# HC-NBIOT_Single_lamp_controller-V1_2.net
KiCad netlist of a schematic drawn in Altium Designer
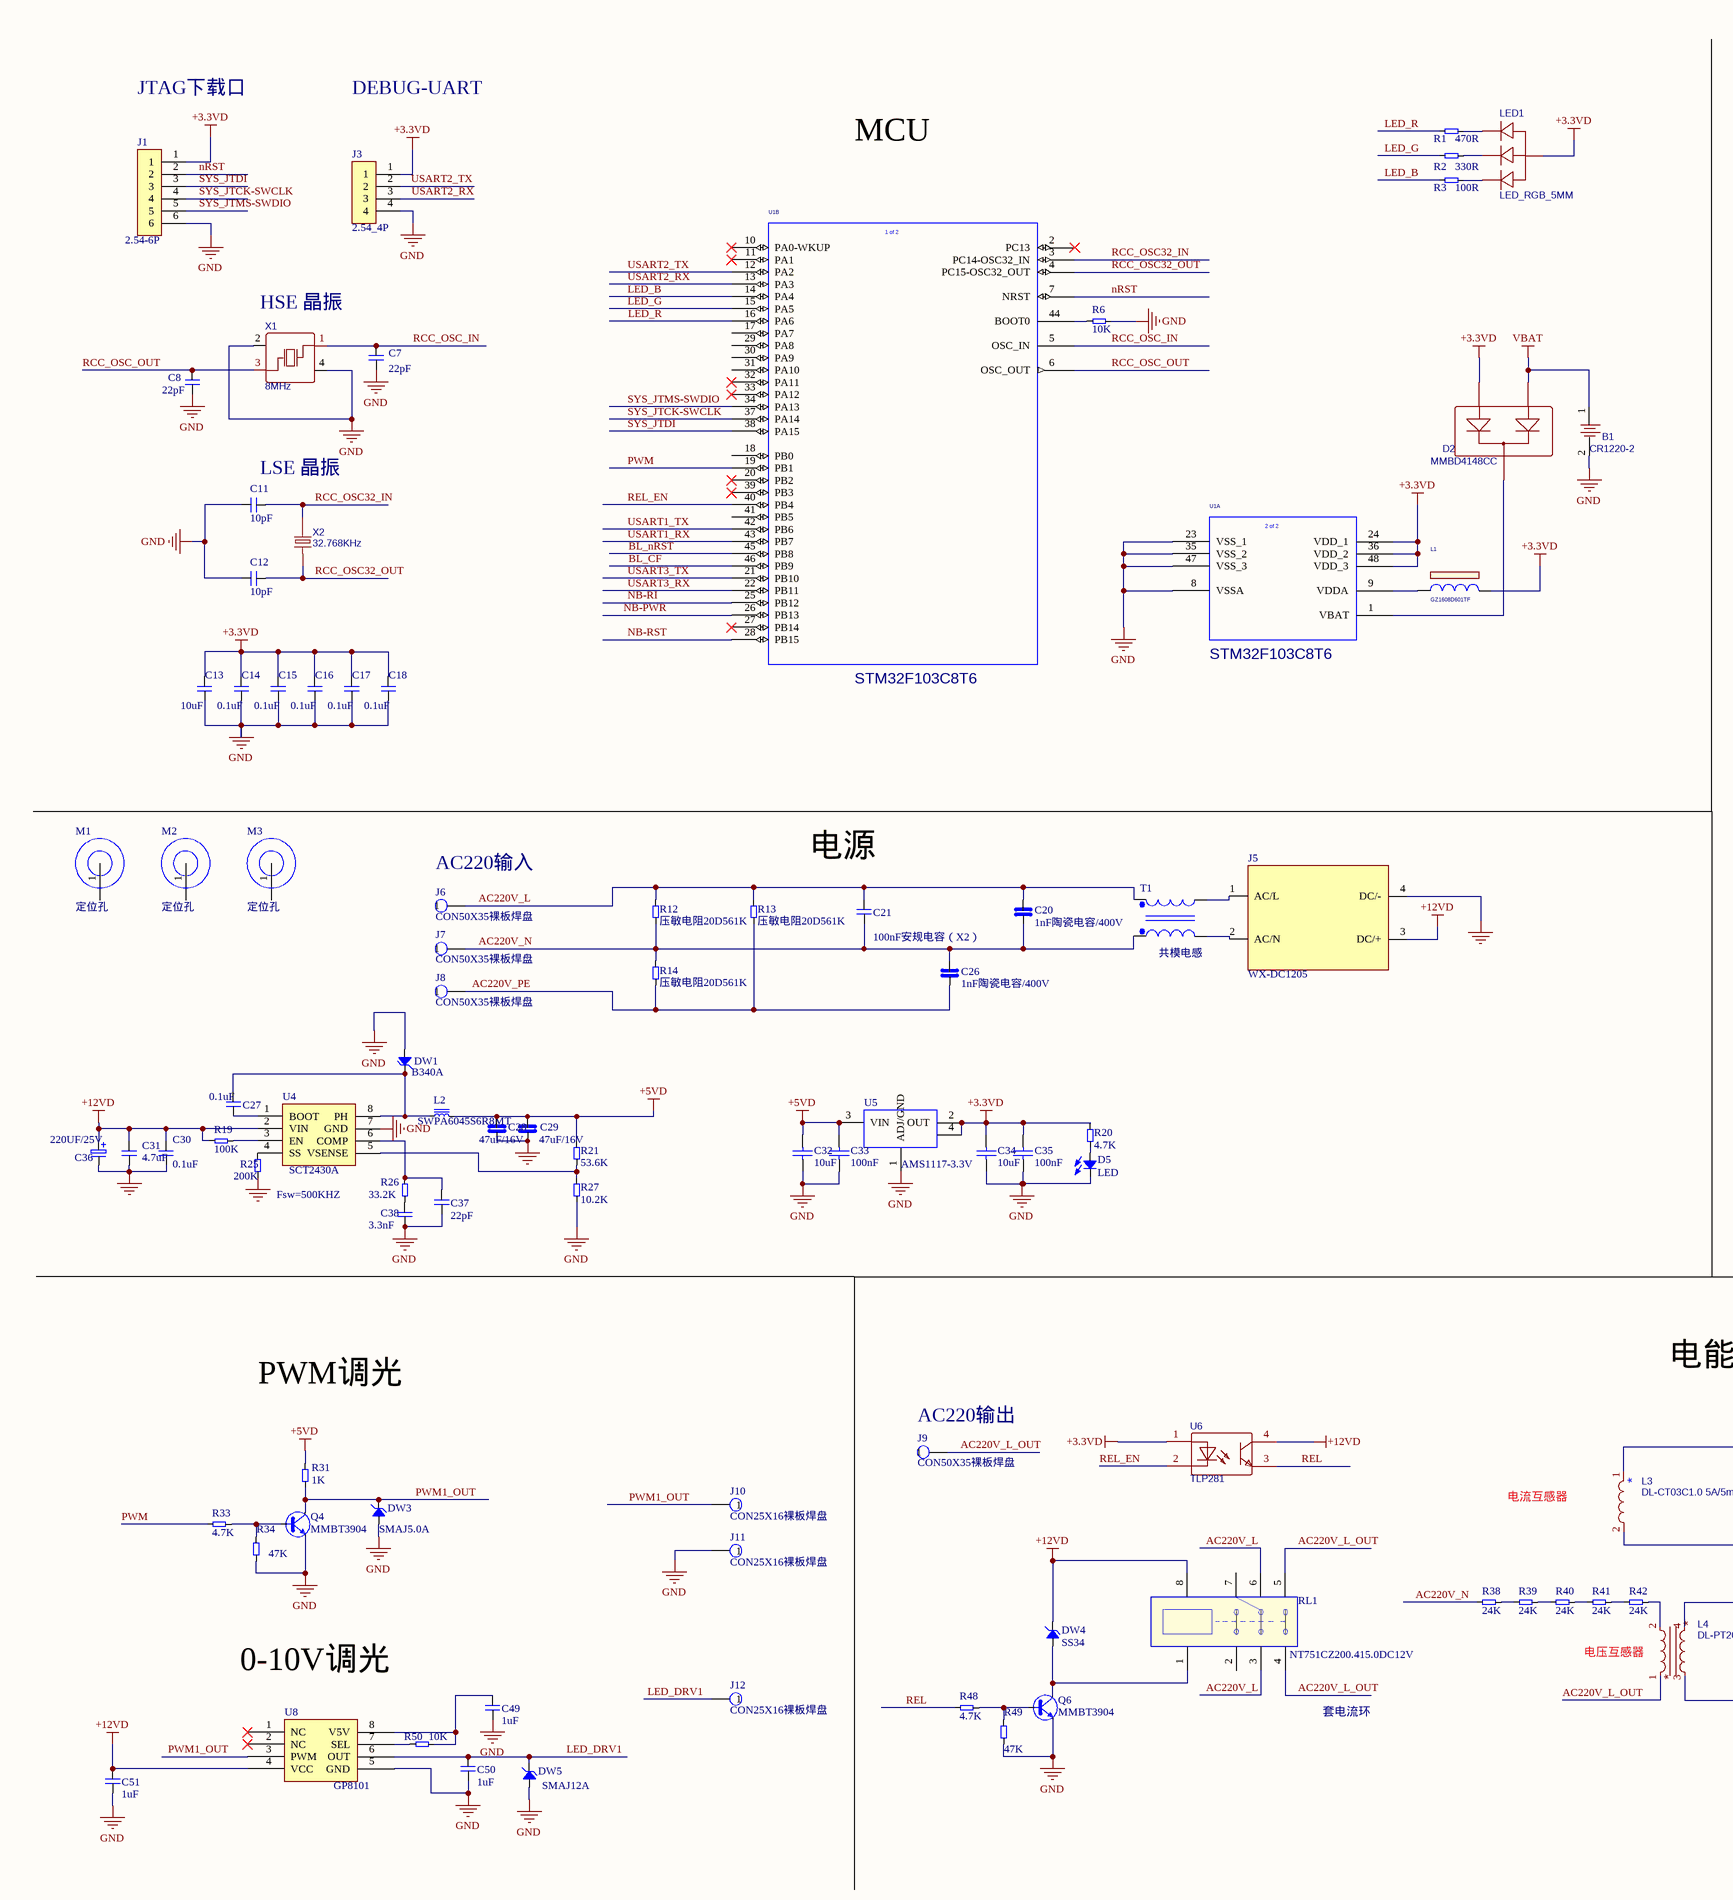
[diagram p0: HC-NBIOT_Single_lamp_controller-V1.2.SchDoc, left]
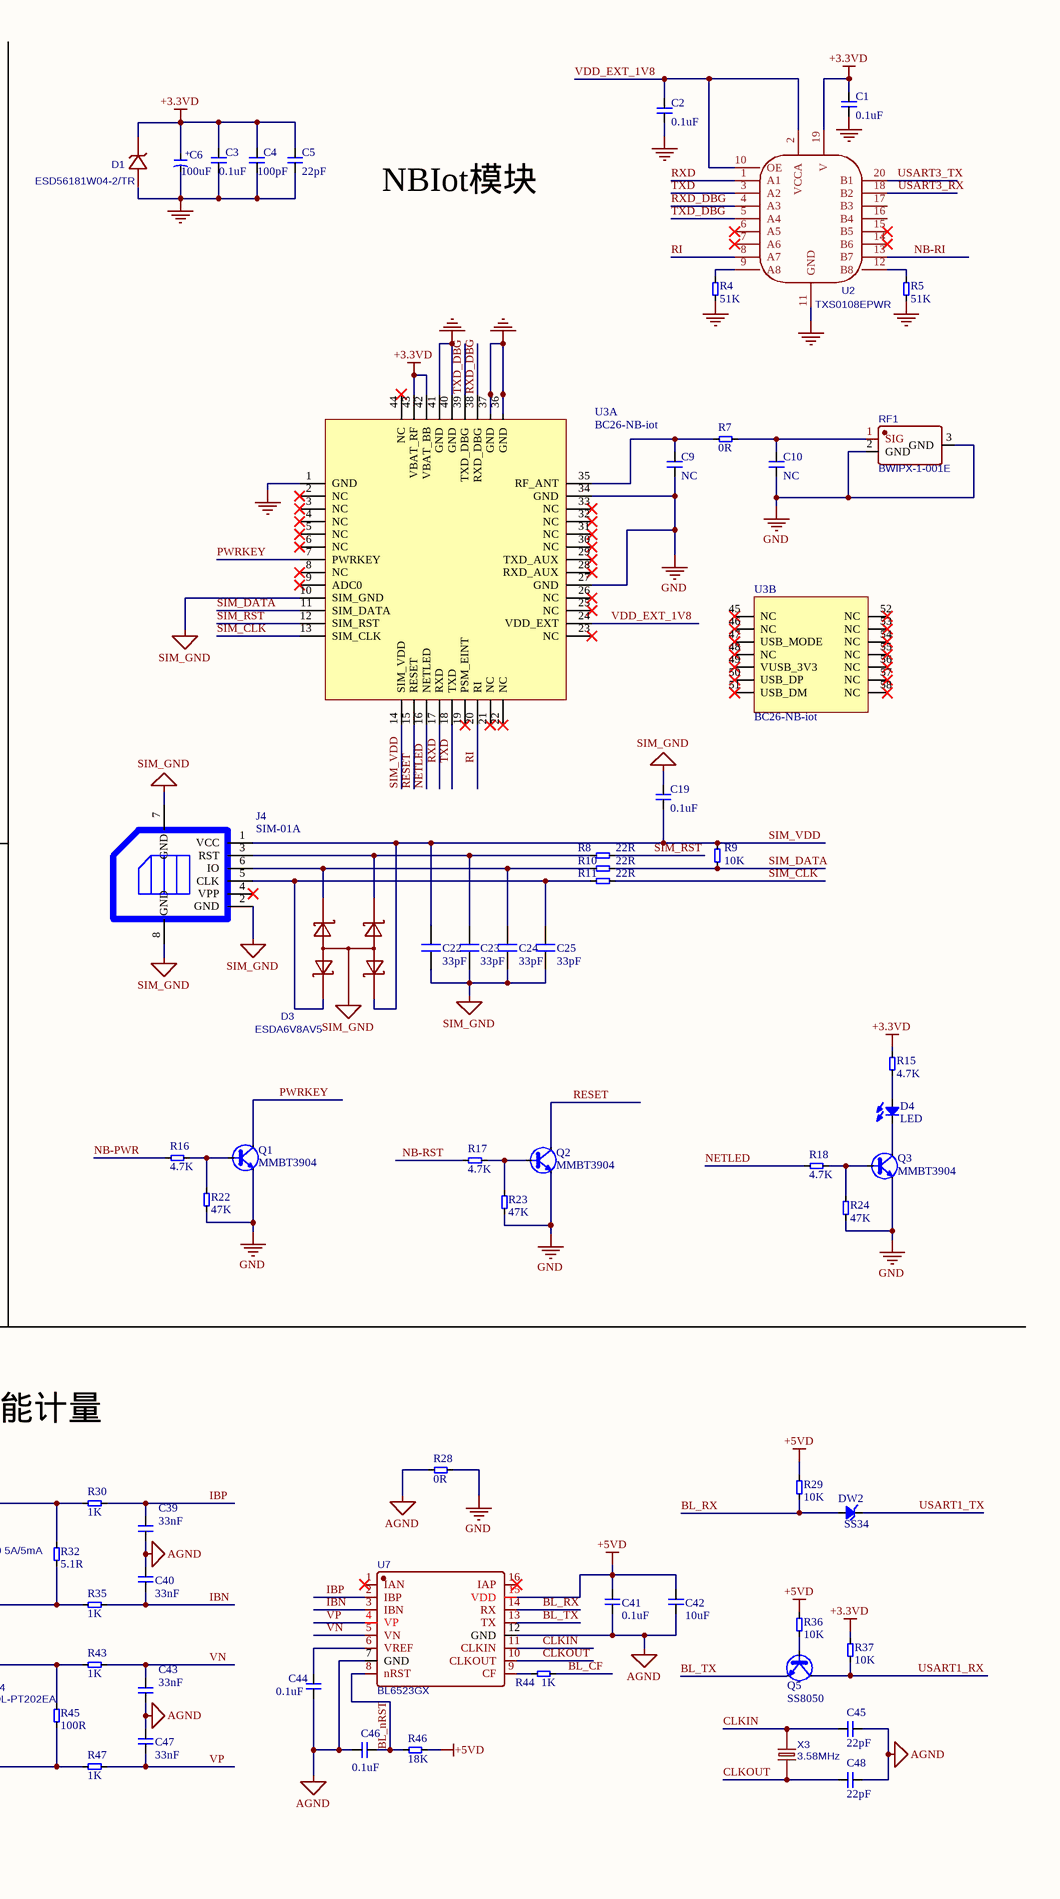
[diagram p1: HC-NBIOT_Single_lamp_controller-V1.2.SchDoc, right]

(export (version "E")
  (design (tool "Eeschema 10.0.6"))
  (components
    (comp (ref "B1")
      (value "CR1220-2")
      (footprint "BAT-SMD_CR1220-2")
      (fields (field (name "BOM_SUPPLIER PART") "C70381"))
      (libsource (lib "czc") (part "CR1220-2"))
    )
    (comp (ref "C1")
      (value "0.1uF")
      (footprint "0603C")
      (description "电容")
      (libsource (lib "DOFAR_AD_LIB") (part "电容"))
    )
    (comp (ref "C2")
      (value "0.1uF")
      (footprint "0603C")
      (description "电容")
      (libsource (lib "DOFAR_AD_LIB") (part "电容"))
    )
    (comp (ref "C3")
      (value "0.1uF")
      (footprint "0603C")
      (description "电容")
      (libsource (lib "DOFAR_AD_LIB") (part "电容"))
    )
    (comp (ref "C4")
      (value "100pF")
      (footprint "0603C")
      (description "电容")
      (libsource (lib "DOFAR_AD_LIB") (part "电容"))
    )
    (comp (ref "C5")
      (value "22pF")
      (footprint "0603C")
      (description "电容")
      (libsource (lib "DOFAR_AD_LIB") (part "电容"))
    )
    (comp (ref "C6")
      (value "100uF")
      (footprint "CAP-SMD_L3.5-W2.8")
      (description "电解电容")
      (libsource (lib "czc") (part "Capacitor"))
    )
    (comp (ref "C7")
      (value "22pF")
      (footprint "0603C")
      (description "电容")
      (libsource (lib "DOFAR_AD_LIB") (part "电容"))
    )
    (comp (ref "C8")
      (value "22pF")
      (footprint "0603C")
      (description "电容")
      (libsource (lib "DOFAR_AD_LIB") (part "电容"))
    )
    (comp (ref "C9")
      (value "NC")
      (footprint "0603C")
      (description "电容")
      (libsource (lib "DOFAR_AD_LIB") (part "电容"))
    )
    (comp (ref "C10")
      (value "NC")
      (footprint "0603C")
      (description "电容")
      (libsource (lib "DOFAR_AD_LIB") (part "电容"))
    )
    (comp (ref "C11")
      (value "10pF")
      (footprint "0603C")
      (description "电容")
      (libsource (lib "DOFAR_AD_LIB") (part "电容"))
    )
    (comp (ref "C12")
      (value "10pF")
      (footprint "0603C")
      (description "电容")
      (libsource (lib "DOFAR_AD_LIB") (part "电容"))
    )
    (comp (ref "C13")
      (value "10uF")
      (footprint "1206C")
      (description "电容")
      (libsource (lib "DOFAR_AD_LIB") (part "电容"))
    )
    (comp (ref "C14")
      (value "0.1uF")
      (footprint "0603C")
      (description "电容")
      (libsource (lib "DOFAR_AD_LIB") (part "电容"))
    )
    (comp (ref "C15")
      (value "0.1uF")
      (footprint "0603C")
      (description "电容")
      (libsource (lib "DOFAR_AD_LIB") (part "电容"))
    )
    (comp (ref "C16")
      (value "0.1uF")
      (footprint "0603C")
      (description "电容")
      (libsource (lib "DOFAR_AD_LIB") (part "电容"))
    )
    (comp (ref "C17")
      (value "0.1uF")
      (footprint "0603C")
      (description "电容")
      (libsource (lib "DOFAR_AD_LIB") (part "电容"))
    )
    (comp (ref "C18")
      (value "0.1uF")
      (footprint "0603C")
      (description "电容")
      (libsource (lib "DOFAR_AD_LIB") (part "电容"))
    )
    (comp (ref "C19")
      (value "0.1uF")
      (footprint "0603C")
      (description "电容")
      (libsource (lib "DOFAR_AD_LIB") (part "电容"))
    )
    (comp (ref "C20")
      (value "1nF陶瓷电容/400V")
      (footprint "1nF/400V")
      (description "多层陶瓷电容")
      (libsource (lib "DF-CBOX-BB_V1.0") (part "多层陶瓷电容"))
    )
    (comp (ref "C21")
      (value "100nF安规电容（X2）")
      (footprint "X2/100nF")
      (description "电容")
      (libsource (lib "DF-CBOX-BB") (part "电容"))
    )
    (comp (ref "C22")
      (value "33pF")
      (footprint "0603C")
      (description "电容")
      (libsource (lib "czc") (part "CAP"))
    )
    (comp (ref "C23")
      (value "33pF")
      (footprint "0603C")
      (description "电容")
      (libsource (lib "czc") (part "CAP"))
    )
    (comp (ref "C24")
      (value "33pF")
      (footprint "0603C")
      (description "电容")
      (libsource (lib "czc") (part "CAP"))
    )
    (comp (ref "C25")
      (value "33pF")
      (footprint "0603C")
      (description "电容")
      (libsource (lib "czc") (part "CAP"))
    )
    (comp (ref "C26")
      (value "1nF陶瓷电容/400V")
      (footprint "1nF/400V")
      (description "多层陶瓷电容")
      (libsource (lib "DF-CBOX-BB_V1.0") (part "多层陶瓷电容"))
    )
    (comp (ref "C27")
      (value "0.1uF")
      (footprint "0603C")
      (description "电容")
      (libsource (lib "DOFAR_AD_LIB") (part "电容"))
    )
    (comp (ref "C28")
      (value "47uF/16V")
      (footprint "1206C")
      (description "多层陶瓷电容")
      (libsource (lib "DOFAR_AD_LIB") (part "多层陶瓷电容"))
    )
    (comp (ref "C29")
      (value "47uF/16V")
      (footprint "1206C")
      (description "多层陶瓷电容")
      (libsource (lib "DOFAR_AD_LIB") (part "多层陶瓷电容"))
    )
    (comp (ref "C30")
      (value "0.1uF")
      (footprint "0603C")
      (description "电容")
      (libsource (lib "DOFAR_AD_LIB") (part "电容"))
    )
    (comp (ref "C31")
      (value "4.7uF")
      (footprint "0603C")
      (description "电容")
      (libsource (lib "*") (part "电容"))
    )
    (comp (ref "C32")
      (value "10uF")
      (footprint "0805C")
      (fields (field (name "PUBLISHER") "Altium Limited"))
      (libsource (lib "Database_AD Library") (part "Cap"))
    )
    (comp (ref "C33")
      (value "100nF")
      (footprint "0603C")
      (fields (field (name "PUBLISHER") "Altium Limited"))
      (libsource (lib "Database_AD Library") (part "Cap"))
    )
    (comp (ref "C34")
      (value "10uF")
      (footprint "0805C")
      (fields (field (name "PUBLISHER") "Altium Limited"))
      (libsource (lib "Database_AD Library") (part "Cap"))
    )
    (comp (ref "C35")
      (value "100nF")
      (footprint "0603C")
      (fields (field (name "PUBLISHER") "Altium Limited"))
      (libsource (lib "Database_AD Library") (part "Cap"))
    )
    (comp (ref "C36")
      (value "220UF/25V")
      (footprint "RAD-3R8")
      (description "电解电容")
      (libsource (lib "DOFAR_AD_LIB") (part "直插电解电容"))
    )
    (comp (ref "C37")
      (value "22pF")
      (footprint "0603C")
      (description "电容")
      (libsource (lib "DOFAR_AD_LIB") (part "电容"))
    )
    (comp (ref "C38")
      (value "3.3nF")
      (footprint "0603C")
      (description "电容")
      (libsource (lib "DOFAR_AD_LIB") (part "电容"))
    )
    (comp (ref "C39")
      (value "33nF")
      (footprint "0603C")
      (description "电容")
      (libsource (lib "DOFAR_AD_LIB") (part "电容"))
    )
    (comp (ref "C40")
      (value "33nF")
      (footprint "0603C")
      (description "电容")
      (libsource (lib "DOFAR_AD_LIB") (part "电容"))
    )
    (comp (ref "C41")
      (value "0.1uF")
      (footprint "0603C")
      (description "电容")
      (libsource (lib "DOFAR_AD_LIB") (part "电容"))
    )
    (comp (ref "C42")
      (value "10uF")
      (footprint "1206C")
      (description "电容")
      (libsource (lib "DOFAR_AD_LIB") (part "电容"))
    )
    (comp (ref "C43")
      (value "33nF")
      (footprint "0603C")
      (description "电容")
      (libsource (lib "DOFAR_AD_LIB") (part "电容"))
    )
    (comp (ref "C44")
      (value "0.1uF")
      (footprint "0603C")
      (description "电容")
      (libsource (lib "DOFAR_AD_LIB") (part "电容"))
    )
    (comp (ref "C45")
      (value "22pF")
      (footprint "0603C")
      (description "电容")
      (libsource (lib "DOFAR_AD_LIB") (part "电容"))
    )
    (comp (ref "C46")
      (value "0.1uF")
      (footprint "0603C")
      (description "电容")
      (libsource (lib "DOFAR_AD_LIB") (part "电容"))
    )
    (comp (ref "C47")
      (value "33nF")
      (footprint "0603C")
      (description "电容")
      (libsource (lib "DOFAR_AD_LIB") (part "电容"))
    )
    (comp (ref "C48")
      (value "22pF")
      (footprint "0603C")
      (description "电容")
      (libsource (lib "DOFAR_AD_LIB") (part "电容"))
    )
    (comp (ref "C49")
      (value "1uF")
      (footprint "0603C")
      (description "电容")
      (libsource (lib "DF-CBOX-MB_V1.0") (part "电容"))
    )
    (comp (ref "C50")
      (value "1uF")
      (footprint "0603C")
      (description "电容")
      (libsource (lib "DF-CBOX-MB_V1.0") (part "电容"))
    )
    (comp (ref "C51")
      (value "1uF")
      (footprint "0603C")
      (description "电容")
      (libsource (lib "DF-CBOX-MB_V1.0") (part "电容"))
    )
    (comp (ref "D1")
      (value "ESD56181W04-2/TR")
      (footprint "ESD56181W04")
      (fields (field (name "BOM_SUPPLIER PART") "C910982") (field (name "CONTRIBUTOR") "LCSC"))
      (libsource (lib "czc") (part "TVS二极管"))
    )
    (comp (ref "D2")
      (value "MMBD4148CC")
      (footprint "SOT-23-3")
      (fields (field (name "BOM_SUPPLIER PART") "C8595"))
      (libsource (lib "czc") (part "MMBD4148CC"))
    )
    (comp (ref "D3")
      (value "ESDA6V8AV5")
      (footprint "SOT-553_ESDA6V8AV5")
      (fields (field (name "BOM_SUPPLIER PART") "C268741") (field (name "CONTRIBUTOR") "LCSC"))
      (libsource (lib "czc") (part "ESDA6V8AV5"))
    )
    (comp (ref "D4") (value "LED") (footprint "LED0603") (libsource (lib "czc") (part "发光二极管")))
    (comp (ref "D5") (value "LED") (footprint "LED0603") (libsource (lib "czc") (part "发光二极管")))
    (comp (ref "DW1") (value "B340A") (footprint "SMB") (libsource (lib "DOFAR_AD_LIB") (part "肖特基二极管")))
    (comp (ref "DW2") (value "SS34") (footprint "SMA") (libsource (lib "DOFAR_AD_LIB") (part "肖特基二极管")))
    (comp (ref "DW3") (value "SMAJ5.0A") (footprint "SMA") (libsource (lib "TIMOR_LIB") (part "肖特基二极管")))
    (comp (ref "DW4") (value "SS34") (footprint "SMA") (libsource (lib "TIMOR_LIB") (part "肖特基二极管")))
    (comp (ref "DW5") (value "SMAJ12A") (footprint "SMA") (libsource (lib "TIMOR_LIB") (part "肖特基二极管")))
    (comp (ref "J1") (value "2.54-6P") (footprint "2.54-6P") (libsource (lib "czc") (part "PIN_6P")))
    (comp (ref "J3") (value "2.54_4P") (footprint "2.54-4P") (libsource (lib "czc") (part "PIN_4P")))
    (comp (ref "J4")
      (value "SIM-01A")
      (footprint "SIM-01A")
      (description "SIM卡座")
      (libsource (lib "czc") (part "SIM-01A"))
    )
    (comp (ref "J5") (value "WX-DC1205") (footprint "WX-DC1205") (libsource (lib "czc") (part "WX-DC1205")))
    (comp (ref "J6")
      (value "CON50X35裸板焊盘")
      (footprint "SCREW5030")
      (libsource (lib "DF-CBOX-BB") (part "CON1X1"))
    )
    (comp (ref "J7")
      (value "CON50X35裸板焊盘")
      (footprint "SCREW5030")
      (libsource (lib "DF-CBOX-BB") (part "CON1X1"))
    )
    (comp (ref "J8")
      (value "CON50X35裸板焊盘")
      (footprint "SCREW5030")
      (libsource (lib "DF-CBOX-BB") (part "CON1X1"))
    )
    (comp (ref "J9")
      (value "CON50X35裸板焊盘")
      (footprint "SCREW5030")
      (libsource (lib "DF-CBOX-BB") (part "CON1X1"))
    )
    (comp (ref "J10")
      (value "CON25X16裸板焊盘")
      (footprint "SCREW2516")
      (libsource (lib "DF-CBOX-BB") (part "CON1X1"))
    )
    (comp (ref "J11")
      (value "CON25X16裸板焊盘")
      (footprint "SCREW2516")
      (libsource (lib "DF-CBOX-BB") (part "CON1X1"))
    )
    (comp (ref "J12")
      (value "CON25X16裸板焊盘")
      (footprint "SCREW2516")
      (libsource (lib "DF-CBOX-BB") (part "CON1X1"))
    )
    (comp (ref "L1")
      (value "GZ1608D601TF")
      (footprint "0603L")
      (description "IND FER BEAD 120 OHM@100MHZ 0.5A 25% 0402")
      (fields (field (name "TOLERANCE") "25%"))
      (libsource (lib "czc") (part "INDUCTOR_FERRITE"))
    )
    (comp (ref "L2")
      (value "SWPA6045S6R8MT")
      (footprint "SDRH6D45")
      (libsource (lib "DOFAR_AD_LIB") (part "功率电感"))
    )
    (comp (ref "L3")
      (value "DL-CT03C1.0 5A/5mA")
      (footprint "DL-CT03C1.0 5A/5mA")
      (fields (field (name "BOM_MANUFACTURER PART") "ZMCT102") (field (name "BOM_SUPPLIER PART") "C84213"))
      (libsource (lib "czc") (part "DL-CT03C1.0 5A/5mA"))
    )
    (comp (ref "L4")
      (value "DL-PT202EA")
      (footprint "DL-PT202EA")
      (fields (field (name "BOM_MANUFACTURER PART") "ZMPT107-1") (field (name "BOM_SUPPLIER PART") "C125191"))
      (libsource (lib "czc") (part "DL-PT202EA"))
    )
    (comp (ref "LED1")
      (value "LED_RGB_5MM")
      (footprint "LED_RGB_5MM")
      (fields
        (field (name "BOM_SUPPLIER PART") "C417349")
        (field (name "BOM_MANUFACTURER PART") "MHLA5319URGBDWT")
        (field (name "CONTRIBUTOR") "LCSC")
      )
      (libsource (lib "czc") (part "LED_REB_5MM"))
    )
    (comp (ref "M1") (value "定位孔") (footprint "SCREW7035") (libsource (lib "typ-lib") (part "定位孔")))
    (comp (ref "M2") (value "定位孔") (footprint "SCREW7035") (libsource (lib "typ-lib") (part "定位孔")))
    (comp (ref "M3") (value "定位孔") (footprint "SCREW7035") (libsource (lib "typ-lib") (part "定位孔")))
    (comp (ref "Q1") (value "MMBT3904") (footprint "SOT-23") (libsource (lib "dofar-lib") (part "MMBT3904")))
    (comp (ref "Q2") (value "MMBT3904") (footprint "SOT-23") (libsource (lib "dofar-lib") (part "MMBT3904")))
    (comp (ref "Q3") (value "MMBT3904") (footprint "SOT-23") (libsource (lib "dofar-lib") (part "MMBT3904")))
    (comp (ref "Q4") (value "MMBT3904") (footprint "SOT-23") (libsource (lib "dofar-lib") (part "MMBT3904")))
    (comp (ref "Q5") (value "SS8050") (footprint "SOT-23") (libsource (lib "dofar-lib") (part "MMBT3904")))
    (comp (ref "Q6") (value "MMBT3904") (footprint "SOT-23") (libsource (lib "dofar-lib") (part "MMBT3904")))
    (comp (ref "R1") (value "470R") (footprint "0603R") (description "电阻") (libsource (lib "*") (part "电阻")))
    (comp (ref "R2") (value "330R") (footprint "0603R") (description "电阻") (libsource (lib "*") (part "电阻")))
    (comp (ref "R3") (value "100R") (footprint "0603R") (description "电阻") (libsource (lib "*") (part "电阻")))
    (comp (ref "R4")
      (value "51K")
      (footprint "0603R")
      (description "电阻")
      (libsource (lib "DOFAR_AD_LIB") (part "电阻"))
    )
    (comp (ref "R5")
      (value "51K")
      (footprint "0603R")
      (description "电阻")
      (libsource (lib "DOFAR_AD_LIB") (part "电阻"))
    )
    (comp (ref "R6") (value "10K") (footprint "0603R") (description "电阻") (libsource (lib "*") (part "电阻")))
    (comp (ref "R7")
      (value "0R")
      (footprint "0603R")
      (description "电阻")
      (libsource (lib "DOFAR_AD_LIB") (part "电阻"))
    )
    (comp (ref "R8")
      (value "22R")
      (footprint "0603R")
      (description "电阻")
      (libsource (lib "DOFAR_AD_LIB") (part "电阻"))
    )
    (comp (ref "R9")
      (value "10K")
      (footprint "0603R")
      (description "电阻")
      (libsource (lib "DOFAR_AD_LIB") (part "电阻"))
    )
    (comp (ref "R10")
      (value "22R")
      (footprint "0603R")
      (description "电阻")
      (libsource (lib "DOFAR_AD_LIB") (part "电阻"))
    )
    (comp (ref "R11")
      (value "22R")
      (footprint "0603R")
      (description "电阻")
      (libsource (lib "DOFAR_AD_LIB") (part "电阻"))
    )
    (comp (ref "R12")
      (value "压敏电阻20D561K")
      (footprint "20D561K")
      (description "电阻")
      (libsource (lib "DF-CBOX-BB") (part "电阻"))
    )
    (comp (ref "R13")
      (value "压敏电阻20D561K")
      (footprint "20D561K")
      (description "电阻")
      (libsource (lib "DF-CBOX-BB") (part "电阻"))
    )
    (comp (ref "R14")
      (value "压敏电阻20D561K")
      (footprint "20D561K")
      (description "电阻")
      (libsource (lib "DF-CBOX-BB") (part "电阻"))
    )
    (comp (ref "R15")
      (value "4.7K")
      (footprint "0603R")
      (description "电阻")
      (libsource (lib "LOUB-AD") (part "电阻"))
    )
    (comp (ref "R16")
      (value "4.7K")
      (footprint "0603R")
      (description "电阻")
      (libsource (lib "LOUB-AD") (part "电阻"))
    )
    (comp (ref "R17")
      (value "4.7K")
      (footprint "0603R")
      (description "电阻")
      (libsource (lib "LOUB-AD") (part "电阻"))
    )
    (comp (ref "R18")
      (value "4.7K")
      (footprint "0603R")
      (description "电阻")
      (libsource (lib "LOUB-AD") (part "电阻"))
    )
    (comp (ref "R19")
      (value "100K")
      (footprint "0603R")
      (description "电阻")
      (libsource (lib "DOFAR_AD_LIB") (part "电阻"))
    )
    (comp (ref "R20") (value "4.7K") (footprint "0603R") (description "电阻") (libsource (lib "*") (part "电阻")))
    (comp (ref "R21")
      (value "53.6K")
      (footprint "0603R")
      (description "电阻")
      (libsource (lib "DOFAR_AD_LIB") (part "电阻"))
    )
    (comp (ref "R22")
      (value "47K")
      (footprint "0603R")
      (description "电阻")
      (libsource (lib "LOUB-AD") (part "电阻"))
    )
    (comp (ref "R23")
      (value "47K")
      (footprint "0603R")
      (description "电阻")
      (libsource (lib "LOUB-AD") (part "电阻"))
    )
    (comp (ref "R24")
      (value "47K")
      (footprint "0603R")
      (description "电阻")
      (libsource (lib "LOUB-AD") (part "电阻"))
    )
    (comp (ref "R25")
      (value "200K")
      (footprint "0603R")
      (description "电阻")
      (libsource (lib "DOFAR_AD_LIB") (part "电阻"))
    )
    (comp (ref "R26")
      (value "33.2K")
      (footprint "0603R")
      (description "电阻")
      (libsource (lib "*") (part "电阻"))
    )
    (comp (ref "R27")
      (value "10.2K")
      (footprint "0603R")
      (description "电阻")
      (libsource (lib "DOFAR_AD_LIB") (part "电阻"))
    )
    (comp (ref "R28")
      (value "0R")
      (footprint "1210R")
      (description "电阻")
      (libsource (lib "LOUB-AD") (part "电阻"))
    )
    (comp (ref "R29")
      (value "10K")
      (footprint "0603R")
      (description "电阻")
      (libsource (lib "LOUB-AD") (part "电阻"))
    )
    (comp (ref "R30")
      (value "1K")
      (footprint "0603R")
      (description "电阻")
      (libsource (lib "LOUB-AD") (part "电阻"))
    )
    (comp (ref "R31")
      (value "1K")
      (footprint "0603R")
      (description "电阻")
      (libsource (lib "dofar-lib") (part "电阻"))
    )
    (comp (ref "R32")
      (value "5.1R")
      (footprint "0603R")
      (description "电阻")
      (libsource (lib "LOUB-AD") (part "电阻"))
    )
    (comp (ref "R33")
      (value "4.7K")
      (footprint "0603R")
      (description "电阻")
      (libsource (lib "DOFAR_AD_LIB") (part "电阻"))
    )
    (comp (ref "R34")
      (value "47K")
      (footprint "0603R")
      (description "电阻")
      (libsource (lib "LOUB-AD") (part "电阻"))
    )
    (comp (ref "R35")
      (value "1K")
      (footprint "0603R")
      (description "电阻")
      (libsource (lib "LOUB-AD") (part "电阻"))
    )
    (comp (ref "R36")
      (value "10K")
      (footprint "0603R")
      (description "电阻")
      (libsource (lib "LOUB-AD") (part "电阻"))
    )
    (comp (ref "R37")
      (value "10K")
      (footprint "0603R")
      (description "电阻")
      (libsource (lib "LOUB-AD") (part "电阻"))
    )
    (comp (ref "R38")
      (value "24K")
      (footprint "0603R")
      (description "电阻")
      (libsource (lib "LOUB-AD") (part "电阻"))
    )
    (comp (ref "R39")
      (value "24K")
      (footprint "0603R")
      (description "电阻")
      (libsource (lib "LOUB-AD") (part "电阻"))
    )
    (comp (ref "R40")
      (value "24K")
      (footprint "0603R")
      (description "电阻")
      (libsource (lib "LOUB-AD") (part "电阻"))
    )
    (comp (ref "R41")
      (value "24K")
      (footprint "0603R")
      (description "电阻")
      (libsource (lib "LOUB-AD") (part "电阻"))
    )
    (comp (ref "R42")
      (value "24K")
      (footprint "0603R")
      (description "电阻")
      (libsource (lib "LOUB-AD") (part "电阻"))
    )
    (comp (ref "R43")
      (value "1K")
      (footprint "0603R")
      (description "电阻")
      (libsource (lib "LOUB-AD") (part "电阻"))
    )
    (comp (ref "R44")
      (value "1K")
      (footprint "0603R")
      (description "电阻")
      (libsource (lib "LOUB-AD") (part "电阻"))
    )
    (comp (ref "R45")
      (value "100R")
      (footprint "0603R")
      (description "电阻")
      (libsource (lib "LOUB-AD") (part "电阻"))
    )
    (comp (ref "R46")
      (value "18K")
      (footprint "0603R")
      (description "电阻")
      (libsource (lib "LOUB-AD") (part "电阻"))
    )
    (comp (ref "R47")
      (value "1K")
      (footprint "0603R")
      (description "电阻")
      (libsource (lib "LOUB-AD") (part "电阻"))
    )
    (comp (ref "R48")
      (value "4.7K")
      (footprint "0603R")
      (description "电阻")
      (libsource (lib "LOUB-AD") (part "电阻"))
    )
    (comp (ref "R49")
      (value "47K")
      (footprint "0603R")
      (description "电阻")
      (libsource (lib "LOUB-AD") (part "电阻"))
    )
    (comp (ref "R50")
      (value "10K")
      (footprint "0603R")
      (description "电阻")
      (libsource (lib "dofar-lib") (part "电阻"))
    )
    (comp (ref "RF1")
      (value "BWIPX-1-001E")
      (footprint "IPEX一代天线座")
      (fields (field (name "BOM_SUPPLIER PART") "C496552") (field (name "CONTRIBUTOR") "LCSC"))
      (libsource (lib "czc") (part "IPEX一代天线座"))
    )
    (comp (ref "RL1")
      (value "NT751CZ200.415.0DC12V")
      (footprint "G2R-2-24VDC")
      (description "Relay")
      (fields (field (name "PUBLISHER") "Altium Limited"))
      (libsource (lib "TIMOR-SCH") (part "Relay-SPDT"))
    )
    (comp (ref "T1") (value "共模电感") (footprint "L-UU9.8") (libsource (lib "DOFAR_AD_LIB") (part "共模电感")))
    (comp (ref "U1")
      (value "STM32F103C8T6")
      (footprint "STM32F103C8T6")
      (fields
        (field (name "MANUFACTURER_PART_NUMBER") "stm32f103cxt2")
        (field (name "< VALUE >") "STM32F103C8T6")
        (field (name "COPYRIGHT") "Copyright (C) 2016 Accelerated Designs. All rights reserved")
      )
      (libsource (lib "czc") (part "STM32F103C8T6"))
    )
    (comp (ref "U2")
      (value "TXS0108EPWR")
      (footprint "TXS0108EPWR")
      (fields (field (name "BOM_SUPPLIER PART") "C17206"))
      (libsource (lib "czc") (part "TXS0108EPWR"))
    )
    (comp (ref "U3") (value "BC26-NB-iot") (footprint "BC26") (libsource (lib "czc") (part "BC26")))
    (comp (ref "U4")
      (value "SCT2430A")
      (footprint "SOIC8EP-1,27")
      (libsource (lib "DOFAR_AD_LIB") (part "TPS54331"))
    )
    (comp (ref "U5")
      (value "AMS1117-3.3V")
      (footprint "SOT_223")
      (libsource (lib "Database_AD Library") (part "LM1117"))
    )
    (comp (ref "U6")
      (value "TLP281")
      (footprint "SMD-4")
      (fields (field (name "BOM_SUPPLIER PART") "C433437") (field (name "CONTRIBUTOR") "LCSC"))
      (libsource (lib "czc") (part "TLP281"))
    )
    (comp (ref "U7")
      (value "BL6523GX")
      (footprint "SOP-16_BL6523GX")
      (fields (field (name "BOM_SUPPLIER PART") "C213392") (field (name "CONTRIBUTOR") "LCSC"))
      (libsource (lib "czc") (part "BL6523GX"))
    )
    (comp (ref "U8")
      (value "GP8101")
      (footprint "SOIC8-1,27")
      (description "PWM 2 ANALOG")
      (libsource (lib "TIMOR-SCH") (part "GP8101"))
    )
    (comp (ref "X1")
      (value "8MHz")
      (footprint "OSC-SMD_4P-25M")
      (fields
        (field (name "BOM_MANUFACTURER PART") "X1E0000210352000G")
        (field (name "BOM_SUPPLIER PART") "C91738")
      )
      (libsource (lib "czc") (part "TSX-3225 25MHz 20pF 10ppm"))
    )
    (comp (ref "X2")
      (value "32.768KHz")
      (footprint "OSC-SMD_2P-32.768K")
      (fields
        (field (name "BOM_MANUFACTURER PART") "SC-32S32.768kHz20PPM7pF")
        (field (name "BOM_SUPPLIER PART") "C97604")
      )
      (libsource (lib "czc") (part "32.768kHz 20PPM 7pF"))
    )
    (comp (ref "X3")
      (value "3.58MHz")
      (footprint "HC-49SMD_3.58M")
      (fields
        (field (name "BOM_MANUFACTURER PART") "SC-32S32.768kHz20PPM7pF")
        (field (name "BOM_SUPPLIER PART") "C97604")
      )
      (libsource (lib "czc") (part "32.768kHz 20PPM 7pF"))
    )
  )
  (nets
    (net (code "1") (name "+3.3VD") (class "Default")
      (node (ref "C1") (pin "1") (pintype "passive"))
      (node (ref "C13") (pin "2") (pintype "passive"))
      (node (ref "C14") (pin "2") (pintype "passive"))
      (node (ref "C15") (pin "2") (pintype "passive"))
      (node (ref "C16") (pin "2") (pintype "passive"))
      (node (ref "C17") (pin "2") (pintype "passive"))
      (node (ref "C18") (pin "2") (pintype "passive"))
      (node (ref "C3") (pin "1") (pintype "passive"))
      (node (ref "C34") (pin "2") (pinfunction "2_2") (pintype "passive"))
      (node (ref "C35") (pin "2") (pinfunction "2_2") (pintype "passive"))
      (node (ref "C4") (pin "1") (pintype "passive"))
      (node (ref "C5") (pin "1") (pintype "passive"))
      (node (ref "C6") (pin "1") (pinfunction "1_1") (pintype "passive"))
      (node (ref "D1") (pin "1") (pinfunction "K_1") (pintype "passive"))
      (node (ref "D2") (pin "2") (pinfunction "2_2") (pintype "passive"))
      (node (ref "J1") (pin "1") (pinfunction "1_1") (pintype "passive"))
      (node (ref "J3") (pin "1") (pinfunction "1_1") (pintype "passive"))
      (node (ref "L1") (pin "2") (pinfunction "2_2") (pintype "passive"))
      (node (ref "LED1") (pin "2") (pinfunction "+_2") (pintype "passive"))
      (node (ref "R15") (pin "2") (pintype "passive"))
      (node (ref "R20") (pin "1") (pintype "passive"))
      (node (ref "R37") (pin "1") (pintype "passive"))
      (node (ref "U1") (pin "24") (pinfunction "VDD_1_24") (pintype "power_in"))
      (node (ref "U1") (pin "36") (pinfunction "VDD_2_36") (pintype "power_in"))
      (node (ref "U1") (pin "48") (pinfunction "VDD_3_48") (pintype "power_in"))
      (node (ref "U2") (pin "19") (pinfunction "V_19") (pintype "passive"))
      (node (ref "U3") (pin "42") (pinfunction "VBAT_BB_42") (pintype "passive"))
      (node (ref "U3") (pin "43") (pinfunction "VBAT_RF_43") (pintype "passive"))
      (node (ref "U5") (pin "2") (pinfunction "OUT_2") (pintype "passive"))
      (node (ref "U5") (pin "4") (pintype "passive"))
      (node (ref "U6") (pin "1") (pinfunction "1_1") (pintype "passive"))
    )
    (net (code "2") (name "+5VD") (class "Default")
      (node (ref "C28") (pin "1") (pintype "passive"))
      (node (ref "C29") (pin "1") (pintype "passive"))
      (node (ref "C32") (pin "2") (pinfunction "2_2") (pintype "passive"))
      (node (ref "C33") (pin "2") (pinfunction "2_2") (pintype "passive"))
      (node (ref "C41") (pin "2") (pintype "passive"))
      (node (ref "C42") (pin "2") (pintype "passive"))
      (node (ref "L2") (pin "2") (pintype "passive"))
      (node (ref "R21") (pin "2") (pintype "passive"))
      (node (ref "R29") (pin "1") (pintype "passive"))
      (node (ref "R31") (pin "2") (pintype "passive"))
      (node (ref "R36") (pin "1") (pintype "passive"))
      (node (ref "R46") (pin "1") (pintype "passive"))
      (node (ref "U5") (pin "3") (pinfunction "VIN_3") (pintype "passive"))
      (node (ref "U7") (pin "15") (pinfunction "VDD_15") (pintype "passive"))
    )
    (net (code "3") (name "+12VD") (class "Default")
      (node (ref "C30") (pin "2") (pintype "passive"))
      (node (ref "C31") (pin "2") (pintype "passive"))
      (node (ref "C36") (pin "1") (pintype "passive"))
      (node (ref "C51") (pin "2") (pintype "passive"))
      (node (ref "DW4") (pin "K") (pintype "passive"))
      (node (ref "J5") (pin "3") (pinfunction "DC/+_3") (pintype "passive"))
      (node (ref "R19") (pin "2") (pintype "passive"))
      (node (ref "RL1") (pin "8") (pinfunction "8_8") (pintype "passive"))
      (node (ref "U4") (pin "2") (pinfunction "VIN_2") (pintype "passive"))
      (node (ref "U6") (pin "4") (pinfunction "4_4") (pintype "passive"))
      (node (ref "U8") (pin "4") (pinfunction "VCC_4") (pintype "passive"))
    )
    (net (code "4") (name "/AC220V_L") (class "Default")
      (node (ref "C20") (pin "1") (pintype "passive"))
      (node (ref "C21") (pin "2") (pintype "passive"))
      (node (ref "J6") (pin "1") (pinfunction "1_1") (pintype "passive"))
      (node (ref "R12") (pin "2") (pintype "passive"))
      (node (ref "R13") (pin "2") (pintype "passive"))
      (node (ref "RL1") (pin "3") (pinfunction "3_3") (pintype "passive"))
      (node (ref "RL1") (pin "6") (pinfunction "6_6") (pintype "passive"))
      (node (ref "T1") (pin "4") (pinfunction "Sec1+_4") (pintype "passive"))
    )
    (net (code "5") (name "/AC220V_L_OUT") (class "Default")
      (node (ref "J9") (pin "1") (pinfunction "1_1") (pintype "passive"))
      (node (ref "L4") (pin "1") (pinfunction "1_1") (pintype "passive"))
      (node (ref "RL1") (pin "4") (pinfunction "4_4") (pintype "passive"))
      (node (ref "RL1") (pin "5") (pinfunction "5_5") (pintype "passive"))
    )
    (net (code "6") (name "/AC220V_N") (class "Default")
      (node (ref "C20") (pin "2") (pintype "passive"))
      (node (ref "C21") (pin "1") (pintype "passive"))
      (node (ref "C26") (pin "1") (pintype "passive"))
      (node (ref "J7") (pin "1") (pinfunction "1_1") (pintype "passive"))
      (node (ref "R12") (pin "1") (pintype "passive"))
      (node (ref "R14") (pin "2") (pintype "passive"))
      (node (ref "R38") (pin "2") (pintype "passive"))
      (node (ref "T1") (pin "1") (pinfunction "Sec2+_1") (pintype "passive"))
    )
    (net (code "7") (name "/AC220V_PE") (class "Default")
      (node (ref "C26") (pin "2") (pintype "passive"))
      (node (ref "J8") (pin "1") (pinfunction "1_1") (pintype "passive"))
      (node (ref "R13") (pin "1") (pintype "passive"))
      (node (ref "R14") (pin "1") (pintype "passive"))
    )
    (net (code "8") (name "/BL_CF") (class "Default")
      (node (ref "R44") (pin "2") (pintype "passive"))
      (node (ref "U1") (pin "46") (pinfunction "PB9_46") (pintype "bidirectional"))
    )
    (net (code "9") (name "/BL_RX") (class "Default")
      (node (ref "DW2") (pin "A") (pintype "passive"))
      (node (ref "R29") (pin "2") (pintype "passive"))
      (node (ref "U7") (pin "14") (pinfunction "RX_14") (pintype "passive"))
    )
    (net (code "10") (name "/BL_TX") (class "Default")
      (node (ref "Q5") (pin "2") (pintype "passive"))
      (node (ref "U7") (pin "13") (pinfunction "TX_13") (pintype "passive"))
    )
    (net (code "11") (name "/BL_nRST") (class "Default")
      (node (ref "C46") (pin "1") (pintype "passive"))
      (node (ref "R46") (pin "2") (pintype "passive"))
      (node (ref "U1") (pin "45") (pinfunction "PB8_45") (pintype "bidirectional"))
      (node (ref "U7") (pin "8") (pinfunction "nRST_8") (pintype "passive"))
    )
    (net (code "12") (name "/CLKIN") (class "Default")
      (node (ref "C45") (pin "2") (pintype "passive"))
      (node (ref "U7") (pin "11") (pinfunction "CLKIN_11") (pintype "passive"))
      (node (ref "X3") (pin "2") (pinfunction "2_2") (pintype "passive"))
    )
    (net (code "13") (name "/CLKOUT") (class "Default")
      (node (ref "C48") (pin "2") (pintype "passive"))
      (node (ref "U7") (pin "10") (pinfunction "CLKOUT_10") (pintype "passive"))
      (node (ref "X3") (pin "1") (pinfunction "1_1") (pintype "passive"))
    )
    (net (code "14") (name "/IBN") (class "Default")
      (node (ref "C40") (pin "2") (pintype "passive"))
      (node (ref "R35") (pin "1") (pintype "passive"))
      (node (ref "U7") (pin "3") (pinfunction "IBN_3") (pintype "passive"))
    )
    (net (code "15") (name "/IBP") (class "Default")
      (node (ref "C39") (pin "2") (pintype "passive"))
      (node (ref "R30") (pin "1") (pintype "passive"))
      (node (ref "U7") (pin "2") (pinfunction "IBP_2") (pintype "passive"))
    )
    (net (code "16") (name "/LED_B") (class "Default")
      (node (ref "R3") (pin "2") (pintype "passive"))
      (node (ref "U1") (pin "14") (pinfunction "PA4_14") (pintype "bidirectional"))
    )
    (net (code "17") (name "/LED_DRV1") (class "Default")
      (node (ref "C50") (pin "2") (pintype "passive"))
      (node (ref "DW5") (pin "K") (pintype "passive"))
      (node (ref "J12") (pin "1") (pinfunction "1_1") (pintype "passive"))
      (node (ref "U8") (pin "6") (pinfunction "OUT_6") (pintype "passive"))
    )
    (net (code "18") (name "/LED_G") (class "Default")
      (node (ref "R2") (pin "2") (pintype "passive"))
      (node (ref "U1") (pin "15") (pinfunction "PA5_15") (pintype "bidirectional"))
    )
    (net (code "19") (name "/LED_R") (class "Default")
      (node (ref "R1") (pin "2") (pintype "passive"))
      (node (ref "U1") (pin "16") (pinfunction "PA6_16") (pintype "bidirectional"))
    )
    (net (code "20") (name "/NB-PWR") (class "Default")
      (node (ref "R16") (pin "1") (pintype "passive"))
      (node (ref "U1") (pin "26") (pinfunction "PB13_26") (pintype "bidirectional"))
    )
    (net (code "21") (name "/NB-RI") (class "Default")
      (node (ref "U1") (pin "25") (pinfunction "PB12_25") (pintype "bidirectional"))
      (node (ref "U2") (pin "13") (pinfunction "B7_13") (pintype "passive"))
    )
    (net (code "22") (name "/NB-RST") (class "Default")
      (node (ref "R17") (pin "1") (pintype "passive"))
      (node (ref "U1") (pin "28") (pinfunction "PB15_28") (pintype "bidirectional"))
    )
    (net (code "23") (name "/NETLED") (class "Default")
      (node (ref "R18") (pin "1") (pintype "passive"))
      (node (ref "U3") (pin "16") (pinfunction "NETLED_16") (pintype "passive"))
    )
    (net (code "24") (name "/PWM") (class "Default")
      (node (ref "R33") (pin "2") (pintype "passive"))
      (node (ref "U1") (pin "19") (pinfunction "PB1_19") (pintype "bidirectional"))
    )
    (net (code "25") (name "/PWM1_OUT") (class "Default")
      (node (ref "DW3") (pin "K") (pintype "passive"))
      (node (ref "J10") (pin "1") (pinfunction "1_1") (pintype "passive"))
      (node (ref "Q4") (pin "3") (pintype "passive"))
      (node (ref "R31") (pin "1") (pintype "passive"))
      (node (ref "U8") (pin "3") (pinfunction "PWM_3") (pintype "passive"))
    )
    (net (code "26") (name "/PWRKEY") (class "Default")
      (node (ref "Q1") (pin "3") (pintype "passive"))
      (node (ref "U3") (pin "7") (pinfunction "PWRKEY_7") (pintype "passive"))
    )
    (net (code "27") (name "/RCC_OSC32_IN") (class "Default")
      (node (ref "C11") (pin "1") (pintype "passive"))
      (node (ref "U1") (pin "3") (pinfunction "PC14-OSC32_IN_3") (pintype "bidirectional"))
      (node (ref "X2") (pin "2") (pinfunction "2_2") (pintype "passive"))
    )
    (net (code "28") (name "/RCC_OSC32_OUT") (class "Default")
      (node (ref "C12") (pin "1") (pintype "passive"))
      (node (ref "U1") (pin "4") (pinfunction "PC15-OSC32_OUT_4") (pintype "bidirectional"))
      (node (ref "X2") (pin "1") (pinfunction "1_1") (pintype "passive"))
    )
    (net (code "29") (name "/RCC_OSC_IN") (class "Default")
      (node (ref "C7") (pin "2") (pintype "passive"))
      (node (ref "U1") (pin "5") (pinfunction "OSC_IN_5") (pintype "passive"))
      (node (ref "X1") (pin "1") (pinfunction "OSC1_1") (pintype "passive"))
    )
    (net (code "30") (name "/RCC_OSC_OUT") (class "Default")
      (node (ref "C8") (pin "2") (pintype "passive"))
      (node (ref "U1") (pin "6") (pinfunction "OSC_OUT_6") (pintype "output"))
      (node (ref "X1") (pin "3") (pinfunction "OSC2_3") (pintype "passive"))
    )
    (net (code "31") (name "/REL") (class "Default")
      (node (ref "R48") (pin "1") (pintype "passive"))
      (node (ref "U6") (pin "3") (pinfunction "3_3") (pintype "passive"))
    )
    (net (code "32") (name "/REL_EN") (class "Default")
      (node (ref "U1") (pin "40") (pinfunction "PB4_40") (pintype "bidirectional"))
      (node (ref "U6") (pin "2") (pinfunction "2_2") (pintype "passive"))
    )
    (net (code "33") (name "/RESET") (class "Default")
      (node (ref "Q2") (pin "3") (pintype "passive"))
      (node (ref "U3") (pin "15") (pinfunction "RESET_15") (pintype "passive"))
    )
    (net (code "34") (name "/RI") (class "Default")
      (node (ref "U2") (pin "8") (pinfunction "A7_8") (pintype "passive"))
      (node (ref "U3") (pin "20") (pinfunction "RI_20") (pintype "passive"))
    )
    (net (code "35") (name "/RXD") (class "Default")
      (node (ref "U2") (pin "1") (pinfunction "A1_1") (pintype "passive"))
      (node (ref "U3") (pin "17") (pinfunction "RXD_17") (pintype "passive"))
    )
    (net (code "36") (name "/RXD_DBG") (class "Default")
      (node (ref "U2") (pin "4") (pinfunction "A3_4") (pintype "passive"))
      (node (ref "U3") (pin "38") (pinfunction "RXD_DBG_38") (pintype "passive"))
    )
    (net (code "37") (name "/SIM_CLK") (class "Default")
      (node (ref "R11") (pin "1") (pintype "passive"))
      (node (ref "U3") (pin "13") (pinfunction "SIM_CLK_13") (pintype "passive"))
    )
    (net (code "38") (name "/SIM_DATA") (class "Default")
      (node (ref "R10") (pin "1") (pintype "passive"))
      (node (ref "R9") (pin "2") (pintype "passive"))
      (node (ref "U3") (pin "11") (pinfunction "SIM_DATA_11") (pintype "passive"))
    )
    (net (code "39") (name "/SIM_RST") (class "Default")
      (node (ref "R8") (pin "1") (pintype "passive"))
      (node (ref "U3") (pin "12") (pinfunction "SIM_RST_12") (pintype "passive"))
    )
    (net (code "40") (name "/SIM_VDD") (class "Default")
      (node (ref "C19") (pin "2") (pintype "passive"))
      (node (ref "C22") (pin "2") (pinfunction "2_2") (pintype "passive"))
      (node (ref "D3") (pin "3") (pinfunction "I/O2_3") (pintype "passive"))
      (node (ref "J4") (pin "1") (pinfunction "VCC_1") (pintype "passive"))
      (node (ref "R9") (pin "1") (pintype "passive"))
      (node (ref "U3") (pin "14") (pinfunction "SIM_VDD_14") (pintype "passive"))
    )
    (net (code "41") (name "/SYS_JTCK-SWCLK") (class "Default")
      (node (ref "J1") (pin "4") (pinfunction "4_4") (pintype "passive"))
      (node (ref "U1") (pin "37") (pinfunction "PA14_37") (pintype "bidirectional"))
    )
    (net (code "42") (name "/SYS_JTDI") (class "Default")
      (node (ref "J1") (pin "3") (pinfunction "3_3") (pintype "passive"))
      (node (ref "U1") (pin "38") (pinfunction "PA15_38") (pintype "bidirectional"))
    )
    (net (code "43") (name "/SYS_JTMS-SWDIO") (class "Default")
      (node (ref "J1") (pin "5") (pinfunction "5_5") (pintype "passive"))
      (node (ref "U1") (pin "34") (pinfunction "PA13_34") (pintype "bidirectional"))
    )
    (net (code "44") (name "/TXD") (class "Default")
      (node (ref "U2") (pin "3") (pinfunction "A2_3") (pintype "passive"))
      (node (ref "U3") (pin "18") (pinfunction "TXD_18") (pintype "passive"))
    )
    (net (code "45") (name "/TXD_DBG") (class "Default")
      (node (ref "U2") (pin "5") (pinfunction "A4_5") (pintype "passive"))
      (node (ref "U3") (pin "39") (pinfunction "TXD_DBG_39") (pintype "passive"))
    )
    (net (code "46") (name "/USART1_RX") (class "Default")
      (node (ref "Q5") (pin "3") (pintype "passive"))
      (node (ref "R37") (pin "2") (pintype "passive"))
      (node (ref "U1") (pin "43") (pinfunction "PB7_43") (pintype "bidirectional"))
    )
    (net (code "47") (name "/USART1_TX") (class "Default")
      (node (ref "DW2") (pin "K") (pintype "passive"))
      (node (ref "U1") (pin "42") (pinfunction "PB6_42") (pintype "bidirectional"))
    )
    (net (code "48") (name "/USART2_RX") (class "Default")
      (node (ref "J3") (pin "3") (pinfunction "3_3") (pintype "passive"))
      (node (ref "U1") (pin "13") (pinfunction "PA3_13") (pintype "bidirectional"))
    )
    (net (code "49") (name "/USART2_TX") (class "Default")
      (node (ref "J3") (pin "2") (pinfunction "2_2") (pintype "passive"))
      (node (ref "U1") (pin "12") (pinfunction "PA2_12") (pintype "bidirectional"))
    )
    (net (code "50") (name "/USART3_RX") (class "Default")
      (node (ref "U1") (pin "22") (pinfunction "PB11_22") (pintype "bidirectional"))
      (node (ref "U2") (pin "18") (pinfunction "B2_18") (pintype "passive"))
    )
    (net (code "51") (name "/USART3_TX") (class "Default")
      (node (ref "U1") (pin "21") (pinfunction "PB10_21") (pintype "bidirectional"))
      (node (ref "U2") (pin "20") (pinfunction "B1_20") (pintype "passive"))
    )
    (net (code "52") (name "/VDD_EXT_1V8") (class "Default")
      (node (ref "C2") (pin "1") (pintype "passive"))
      (node (ref "U2") (pin "10") (pinfunction "OE_10") (pintype "passive"))
      (node (ref "U2") (pin "2") (pinfunction "VCCA_2") (pintype "passive"))
      (node (ref "U3") (pin "24") (pinfunction "VDD_EXT_24") (pintype "passive"))
    )
    (net (code "53") (name "/VN") (class "Default")
      (node (ref "C43") (pin "2") (pintype "passive"))
      (node (ref "R43") (pin "1") (pintype "passive"))
      (node (ref "U7") (pin "5") (pinfunction "VN_5") (pintype "passive"))
    )
    (net (code "54") (name "/VP") (class "Default")
      (node (ref "C47") (pin "2") (pintype "passive"))
      (node (ref "R47") (pin "1") (pintype "passive"))
      (node (ref "U7") (pin "4") (pinfunction "VP_4") (pintype "passive"))
    )
    (net (code "55") (name "/nRST") (class "Default")
      (node (ref "J1") (pin "2") (pinfunction "2_2") (pintype "passive"))
      (node (ref "U1") (pin "7") (pinfunction "NRST_7") (pintype "bidirectional"))
    )
    (net (code "56") (name "AGND") (class "Default")
      (node (ref "C39") (pin "1") (pintype "passive"))
      (node (ref "C40") (pin "1") (pintype "passive"))
      (node (ref "C41") (pin "1") (pintype "passive"))
      (node (ref "C42") (pin "1") (pintype "passive"))
      (node (ref "C43") (pin "1") (pintype "passive"))
      (node (ref "C44") (pin "1") (pintype "passive"))
      (node (ref "C45") (pin "1") (pintype "passive"))
      (node (ref "C46") (pin "2") (pintype "passive"))
      (node (ref "C47") (pin "1") (pintype "passive"))
      (node (ref "C48") (pin "1") (pintype "passive"))
      (node (ref "R28") (pin "1") (pintype "passive"))
      (node (ref "U7") (pin "12") (pinfunction "GND_12") (pintype "passive"))
      (node (ref "U7") (pin "7") (pinfunction "GND_7") (pintype "passive"))
    )
    (net (code "57") (name "GND") (class "Default")
      (node (ref "B1") (pin "2") (pinfunction "2_2") (pintype "passive"))
      (node (ref "C1") (pin "2") (pintype "passive"))
      (node (ref "C10") (pin "2") (pintype "passive"))
      (node (ref "C11") (pin "2") (pintype "passive"))
      (node (ref "C12") (pin "2") (pintype "passive"))
      (node (ref "C13") (pin "1") (pintype "passive"))
      (node (ref "C14") (pin "1") (pintype "passive"))
      (node (ref "C15") (pin "1") (pintype "passive"))
      (node (ref "C16") (pin "1") (pintype "passive"))
      (node (ref "C17") (pin "1") (pintype "passive"))
      (node (ref "C18") (pin "1") (pintype "passive"))
      (node (ref "C2") (pin "2") (pintype "passive"))
      (node (ref "C28") (pin "2") (pintype "passive"))
      (node (ref "C29") (pin "2") (pintype "passive"))
      (node (ref "C3") (pin "2") (pintype "passive"))
      (node (ref "C30") (pin "1") (pintype "passive"))
      (node (ref "C31") (pin "1") (pintype "passive"))
      (node (ref "C32") (pin "1") (pinfunction "1_1") (pintype "passive"))
      (node (ref "C33") (pin "1") (pinfunction "1_1") (pintype "passive"))
      (node (ref "C34") (pin "1") (pinfunction "1_1") (pintype "passive"))
      (node (ref "C35") (pin "1") (pinfunction "1_1") (pintype "passive"))
      (node (ref "C36") (pin "2") (pintype "passive"))
      (node (ref "C37") (pin "1") (pintype "passive"))
      (node (ref "C38") (pin "1") (pintype "passive"))
      (node (ref "C4") (pin "2") (pintype "passive"))
      (node (ref "C49") (pin "1") (pintype "passive"))
      (node (ref "C5") (pin "2") (pintype "passive"))
      (node (ref "C50") (pin "1") (pintype "passive"))
      (node (ref "C51") (pin "1") (pintype "passive"))
      (node (ref "C6") (pin "2") (pinfunction "2_2") (pintype "passive"))
      (node (ref "C7") (pin "1") (pintype "passive"))
      (node (ref "C8") (pin "1") (pintype "passive"))
      (node (ref "C9") (pin "2") (pintype "passive"))
      (node (ref "D1") (pin "2") (pinfunction "A_2") (pintype "passive"))
      (node (ref "D5") (pin "1") (pinfunction "1_1") (pintype "passive"))
      (node (ref "DW1") (pin "A") (pintype "passive"))
      (node (ref "DW3") (pin "A") (pintype "passive"))
      (node (ref "DW5") (pin "A") (pintype "passive"))
      (node (ref "J1") (pin "6") (pinfunction "6_6") (pintype "passive"))
      (node (ref "J11") (pin "1") (pinfunction "1_1") (pintype "passive"))
      (node (ref "J3") (pin "4") (pinfunction "4_4") (pintype "passive"))
      (node (ref "J5") (pin "4") (pinfunction "DC/-_4") (pintype "passive"))
      (node (ref "Q1") (pin "2") (pintype "passive"))
      (node (ref "Q2") (pin "2") (pintype "passive"))
      (node (ref "Q3") (pin "2") (pintype "passive"))
      (node (ref "Q4") (pin "2") (pintype "passive"))
      (node (ref "Q6") (pin "2") (pintype "passive"))
      (node (ref "R22") (pin "1") (pintype "passive"))
      (node (ref "R23") (pin "1") (pintype "passive"))
      (node (ref "R24") (pin "1") (pintype "passive"))
      (node (ref "R25") (pin "1") (pintype "passive"))
      (node (ref "R27") (pin "1") (pintype "passive"))
      (node (ref "R28") (pin "2") (pintype "passive"))
      (node (ref "R34") (pin "1") (pintype "passive"))
      (node (ref "R4") (pin "1") (pintype "passive"))
      (node (ref "R49") (pin "1") (pintype "passive"))
      (node (ref "R5") (pin "1") (pintype "passive"))
      (node (ref "R6") (pin "1") (pintype "passive"))
      (node (ref "RF1") (pin "2") (pinfunction "GND_2") (pintype "passive"))
      (node (ref "RF1") (pin "3") (pinfunction "GND_3") (pintype "passive"))
      (node (ref "U1") (pin "23") (pinfunction "VSS_1_23") (pintype "power_in"))
      (node (ref "U1") (pin "35") (pinfunction "VSS_2_35") (pintype "power_in"))
      (node (ref "U1") (pin "47") (pinfunction "VSS_3_47") (pintype "power_in"))
      (node (ref "U1") (pin "8") (pinfunction "VSSA_8") (pintype "power_in"))
      (node (ref "U2") (pin "11") (pinfunction "GND_11") (pintype "passive"))
      (node (ref "U3") (pin "1") (pinfunction "GND_1") (pintype "passive"))
      (node (ref "U3") (pin "27") (pinfunction "GND_27") (pintype "passive"))
      (node (ref "U3") (pin "34") (pinfunction "GND_34") (pintype "passive"))
      (node (ref "U3") (pin "36") (pinfunction "GND_36") (pintype "passive"))
      (node (ref "U3") (pin "37") (pinfunction "GND_37") (pintype "passive"))
      (node (ref "U3") (pin "40") (pinfunction "GND_40") (pintype "passive"))
      (node (ref "U3") (pin "41") (pinfunction "GND_41") (pintype "passive"))
      (node (ref "U4") (pin "7") (pinfunction "GND_7") (pintype "passive"))
      (node (ref "U5") (pin "1") (pinfunction "ADJ/GND_1") (pintype "passive"))
      (node (ref "U8") (pin "5") (pinfunction "GND_5") (pintype "passive"))
      (node (ref "X1") (pin "2") (pinfunction "GND_2") (pintype "passive"))
      (node (ref "X1") (pin "4") (pinfunction "GND_4") (pintype "passive"))
    )
    (net (code "58") (name "Net-(C38-Pad2)") (class "Default")
      (node (ref "C38") (pin "2") (pintype "passive"))
      (node (ref "R26") (pin "1") (pintype "passive"))
    )
    (net (code "59") (name "Net-(D3-I{slash}O1)") (class "Default")
      (node (ref "C25") (pin "2") (pinfunction "2_2") (pintype "passive"))
      (node (ref "D3") (pin "1") (pinfunction "I/O1_1") (pintype "passive"))
      (node (ref "J4") (pin "5") (pinfunction "CLK_5") (pintype "passive"))
      (node (ref "R11") (pin "2") (pintype "passive"))
    )
    (net (code "60") (name "Net-(D3-I{slash}O3)") (class "Default")
      (node (ref "C23") (pin "2") (pinfunction "2_2") (pintype "passive"))
      (node (ref "D3") (pin "4") (pinfunction "I/O3_4") (pintype "passive"))
      (node (ref "J4") (pin "3") (pinfunction "RST_3") (pintype "passive"))
      (node (ref "R8") (pin "2") (pintype "passive"))
    )
    (net (code "61") (name "Net-(D3-I{slash}O4)") (class "Default")
      (node (ref "C24") (pin "2") (pinfunction "2_2") (pintype "passive"))
      (node (ref "D3") (pin "5") (pinfunction "I/O4_5") (pintype "passive"))
      (node (ref "J4") (pin "6") (pinfunction "IO_6") (pintype "passive"))
      (node (ref "R10") (pin "2") (pintype "passive"))
    )
    (net (code "62") (name "Net-(D4-Pad1)") (class "Default")
      (node (ref "D4") (pin "1") (pinfunction "1_1") (pintype "passive"))
      (node (ref "Q3") (pin "3") (pintype "passive"))
    )
    (net (code "63") (name "Net-(D4-Pad2)") (class "Default")
      (node (ref "D4") (pin "2") (pinfunction "2_2") (pintype "passive"))
      (node (ref "R15") (pin "1") (pintype "passive"))
    )
    (net (code "64") (name "Net-(D5-Pad2)") (class "Default")
      (node (ref "D5") (pin "2") (pinfunction "2_2") (pintype "passive"))
      (node (ref "R20") (pin "2") (pintype "passive"))
    )
    (net (code "65") (name "Net-(DW4-PadA)") (class "Default")
      (node (ref "DW4") (pin "A") (pintype "passive"))
      (node (ref "Q6") (pin "3") (pintype "passive"))
      (node (ref "RL1") (pin "1") (pinfunction "1_1") (pintype "passive"))
    )
    (net (code "66") (name "Net-(J5-AC{slash}L)") (class "Default")
      (node (ref "J5") (pin "1") (pinfunction "AC/L_1") (pintype "passive"))
      (node (ref "T1") (pin "3") (pinfunction "Sec1-_3") (pintype "passive"))
    )
    (net (code "67") (name "Net-(J5-AC{slash}N)") (class "Default")
      (node (ref "J5") (pin "2") (pinfunction "AC/N_2") (pintype "passive"))
      (node (ref "T1") (pin "2") (pinfunction "Sec2-_2") (pintype "passive"))
    )
    (net (code "68") (name "Net-(L3-Pad1)") (class "Default")
      (node (ref "L3") (pin "1") (pinfunction "1_1") (pintype "passive"))
      (node (ref "R30") (pin "2") (pintype "passive"))
      (node (ref "R32") (pin "2") (pintype "passive"))
    )
    (net (code "69") (name "Net-(L3-Pad2)") (class "Default")
      (node (ref "L3") (pin "2") (pinfunction "2_2") (pintype "passive"))
      (node (ref "R32") (pin "1") (pintype "passive"))
      (node (ref "R35") (pin "2") (pintype "passive"))
    )
    (net (code "70") (name "Net-(L4-Pad2)") (class "Default")
      (node (ref "L4") (pin "2") (pinfunction "2_2") (pintype "passive"))
      (node (ref "R42") (pin "1") (pintype "passive"))
    )
    (net (code "71") (name "Net-(L4-Pad3)") (class "Default")
      (node (ref "L4") (pin "3") (pinfunction "3_3") (pintype "passive"))
      (node (ref "R45") (pin "1") (pintype "passive"))
      (node (ref "R47") (pin "2") (pintype "passive"))
    )
    (net (code "72") (name "Net-(L4-Pad4)") (class "Default")
      (node (ref "L4") (pin "4") (pinfunction "4_4") (pintype "passive"))
      (node (ref "R43") (pin "2") (pintype "passive"))
      (node (ref "R45") (pin "2") (pintype "passive"))
    )
    (net (code "73") (name "Net-(LED1---Pad1)") (class "Default")
      (node (ref "LED1") (pin "1") (pinfunction "-_1") (pintype "passive"))
      (node (ref "R1") (pin "1") (pintype "passive"))
    )
    (net (code "74") (name "Net-(LED1---Pad3)") (class "Default")
      (node (ref "LED1") (pin "3") (pinfunction "-_3") (pintype "passive"))
      (node (ref "R2") (pin "1") (pintype "passive"))
    )
    (net (code "75") (name "Net-(LED1---Pad4)") (class "Default")
      (node (ref "LED1") (pin "4") (pinfunction "-_4") (pintype "passive"))
      (node (ref "R3") (pin "1") (pintype "passive"))
    )
    (net (code "76") (name "Net-(Q1-Pad1)") (class "Default")
      (node (ref "Q1") (pin "1") (pinfunction "1_1") (pintype "passive"))
      (node (ref "R16") (pin "2") (pintype "passive"))
      (node (ref "R22") (pin "2") (pintype "passive"))
    )
    (net (code "77") (name "Net-(Q2-Pad1)") (class "Default")
      (node (ref "Q2") (pin "1") (pinfunction "1_1") (pintype "passive"))
      (node (ref "R17") (pin "2") (pintype "passive"))
      (node (ref "R23") (pin "2") (pintype "passive"))
    )
    (net (code "78") (name "Net-(Q3-Pad1)") (class "Default")
      (node (ref "Q3") (pin "1") (pinfunction "1_1") (pintype "passive"))
      (node (ref "R18") (pin "2") (pintype "passive"))
      (node (ref "R24") (pin "2") (pintype "passive"))
    )
    (net (code "79") (name "Net-(Q4-Pad1)") (class "Default")
      (node (ref "Q4") (pin "1") (pinfunction "1_1") (pintype "passive"))
      (node (ref "R33") (pin "1") (pintype "passive"))
      (node (ref "R34") (pin "2") (pintype "passive"))
    )
    (net (code "80") (name "Net-(Q5-Pad1)") (class "Default")
      (node (ref "Q5") (pin "1") (pinfunction "1_1") (pintype "passive"))
      (node (ref "R36") (pin "2") (pintype "passive"))
    )
    (net (code "81") (name "Net-(Q6-Pad1)") (class "Default")
      (node (ref "Q6") (pin "1") (pinfunction "1_1") (pintype "passive"))
      (node (ref "R48") (pin "2") (pintype "passive"))
      (node (ref "R49") (pin "2") (pintype "passive"))
    )
    (net (code "82") (name "Net-(R38-Pad1)") (class "Default")
      (node (ref "R38") (pin "1") (pintype "passive"))
      (node (ref "R39") (pin "2") (pintype "passive"))
    )
    (net (code "83") (name "Net-(R39-Pad1)") (class "Default")
      (node (ref "R39") (pin "1") (pintype "passive"))
      (node (ref "R40") (pin "2") (pintype "passive"))
    )
    (net (code "84") (name "Net-(R40-Pad1)") (class "Default")
      (node (ref "R40") (pin "1") (pintype "passive"))
      (node (ref "R41") (pin "2") (pintype "passive"))
    )
    (net (code "85") (name "Net-(R41-Pad1)") (class "Default")
      (node (ref "R41") (pin "1") (pintype "passive"))
      (node (ref "R42") (pin "2") (pintype "passive"))
    )
    (net (code "86") (name "Net-(RF1-SIG)") (class "Default")
      (node (ref "C10") (pin "1") (pintype "passive"))
      (node (ref "R7") (pin "1") (pintype "passive"))
      (node (ref "RF1") (pin "1") (pinfunction "SIG_1") (pintype "passive"))
    )
    (net (code "87") (name "Net-(U1A-VBAT)") (class "Default")
      (node (ref "D2") (pin "3") (pinfunction "3_3") (pintype "passive"))
      (node (ref "U1") (pin "1") (pinfunction "VBAT_1") (pintype "power_in"))
    )
    (net (code "88") (name "Net-(U1A-VDDA)") (class "Default")
      (node (ref "L1") (pin "1") (pinfunction "1_1") (pintype "passive"))
      (node (ref "U1") (pin "9") (pinfunction "VDDA_9") (pintype "power_in"))
    )
    (net (code "89") (name "Net-(U1B-BOOT0)") (class "Default")
      (node (ref "R6") (pin "2") (pintype "passive"))
      (node (ref "U1") (pin "44") (pinfunction "BOOT0_44") (pintype "passive"))
    )
    (net (code "90") (name "Net-(U2-A8)") (class "Default")
      (node (ref "R4") (pin "2") (pintype "passive"))
      (node (ref "U2") (pin "9") (pinfunction "A8_9") (pintype "passive"))
    )
    (net (code "91") (name "Net-(U2-B8)") (class "Default")
      (node (ref "R5") (pin "2") (pintype "passive"))
      (node (ref "U2") (pin "12") (pinfunction "B8_12") (pintype "passive"))
    )
    (net (code "92") (name "Net-(U3A-RF_ANT)") (class "Default")
      (node (ref "C9") (pin "1") (pintype "passive"))
      (node (ref "R7") (pin "2") (pintype "passive"))
      (node (ref "U3") (pin "35") (pinfunction "RF_ANT_35") (pintype "passive"))
    )
    (net (code "93") (name "Net-(U4-BOOT)") (class "Default")
      (node (ref "C27") (pin "1") (pintype "passive"))
      (node (ref "U4") (pin "1") (pinfunction "BOOT_1") (pintype "passive"))
    )
    (net (code "94") (name "Net-(U4-COMP)") (class "Default")
      (node (ref "C37") (pin "2") (pintype "passive"))
      (node (ref "R26") (pin "2") (pintype "passive"))
      (node (ref "U4") (pin "6") (pinfunction "COMP_6") (pintype "passive"))
    )
    (net (code "95") (name "Net-(U4-EN)") (class "Default")
      (node (ref "R19") (pin "1") (pintype "passive"))
      (node (ref "U4") (pin "3") (pinfunction "EN_3") (pintype "passive"))
    )
    (net (code "96") (name "Net-(U4-PH)") (class "Default")
      (node (ref "C27") (pin "2") (pintype "passive"))
      (node (ref "DW1") (pin "K") (pintype "passive"))
      (node (ref "L2") (pin "1") (pintype "passive"))
      (node (ref "U4") (pin "8") (pinfunction "PH_8") (pintype "passive"))
    )
    (net (code "97") (name "Net-(U4-SS)") (class "Default")
      (node (ref "R25") (pin "2") (pintype "passive"))
      (node (ref "U4") (pin "4") (pinfunction "SS_4") (pintype "passive"))
    )
    (net (code "98") (name "Net-(U4-VSENSE)") (class "Default")
      (node (ref "R21") (pin "1") (pintype "passive"))
      (node (ref "R27") (pin "2") (pintype "passive"))
      (node (ref "U4") (pin "5") (pinfunction "VSENSE_5") (pintype "passive"))
    )
    (net (code "99") (name "Net-(U7-CF)") (class "Default")
      (node (ref "R44") (pin "1") (pintype "passive"))
      (node (ref "U7") (pin "9") (pinfunction "CF_9") (pintype "passive"))
    )
    (net (code "100") (name "Net-(U7-VREF)") (class "Default")
      (node (ref "C44") (pin "2") (pintype "passive"))
      (node (ref "U7") (pin "6") (pinfunction "VREF_6") (pintype "passive"))
    )
    (net (code "101") (name "Net-(U8-SEL)") (class "Default")
      (node (ref "R50") (pin "1") (pintype "passive"))
      (node (ref "U8") (pin "7") (pinfunction "SEL_7") (pintype "passive"))
    )
    (net (code "102") (name "Net-(U8-V5V)") (class "Default")
      (node (ref "C49") (pin "2") (pintype "passive"))
      (node (ref "R50") (pin "2") (pintype "passive"))
      (node (ref "U8") (pin "8") (pinfunction "V5V_8") (pintype "passive"))
    )
    (net (code "103") (name "SIM_GND") (class "Default")
      (node (ref "C19") (pin "1") (pintype "passive"))
      (node (ref "C22") (pin "1") (pinfunction "1_1") (pintype "passive"))
      (node (ref "C23") (pin "1") (pinfunction "1_1") (pintype "passive"))
      (node (ref "C24") (pin "1") (pinfunction "1_1") (pintype "passive"))
      (node (ref "C25") (pin "1") (pinfunction "1_1") (pintype "passive"))
      (node (ref "D3") (pin "2") (pinfunction "GND_2") (pintype "passive"))
      (node (ref "J4") (pin "2") (pinfunction "GND_2") (pintype "passive"))
      (node (ref "J4") (pin "7") (pinfunction "GND_7") (pintype "passive"))
      (node (ref "J4") (pin "8") (pinfunction "GND_8") (pintype "passive"))
      (node (ref "U3") (pin "10") (pinfunction "SIM_GND_10") (pintype "passive"))
    )
    (net (code "104") (name "VBAT") (class "Default")
      (node (ref "B1") (pin "1") (pinfunction "1_1") (pintype "passive"))
      (node (ref "D2") (pin "1") (pinfunction "1_1") (pintype "passive"))
    )
    (net (code "105") (name "unconnected-(J4-VPP-Pad4)") (class "Default")
      (node (ref "J4") (pin "4") (pinfunction "VPP_4") (pintype "passive+no_connect"))
    )
    (net (code "106") (name "unconnected-(M1-Pad1)") (class "Default")
      (node (ref "M1") (pin "1") (pintype "passive"))
    )
    (net (code "107") (name "unconnected-(M2-Pad1)") (class "Default")
      (node (ref "M2") (pin "1") (pintype "passive"))
    )
    (net (code "108") (name "unconnected-(M3-Pad1)") (class "Default")
      (node (ref "M3") (pin "1") (pintype "passive"))
    )
    (net (code "109") (name "unconnected-(RL1-Pad2)") (class "Default")
      (node (ref "RL1") (pin "2") (pinfunction "2_2") (pintype "passive"))
    )
    (net (code "110") (name "unconnected-(RL1-Pad7)") (class "Default")
      (node (ref "RL1") (pin "7") (pinfunction "7_7") (pintype "passive"))
    )
    (net (code "111") (name "unconnected-(U1B-PA0-WKUP-Pad10)") (class "Default")
      (node (ref "U1") (pin "10") (pinfunction "PA0-WKUP_10") (pintype "bidirectional+no_connect"))
    )
    (net (code "112") (name "unconnected-(U1B-PA1-Pad11)") (class "Default")
      (node (ref "U1") (pin "11") (pinfunction "PA1_11") (pintype "bidirectional+no_connect"))
    )
    (net (code "113") (name "unconnected-(U1B-PA7-Pad17)") (class "Default")
      (node (ref "U1") (pin "17") (pinfunction "PA7_17") (pintype "bidirectional"))
    )
    (net (code "114") (name "unconnected-(U1B-PA8-Pad29)") (class "Default")
      (node (ref "U1") (pin "29") (pinfunction "PA8_29") (pintype "bidirectional"))
    )
    (net (code "115") (name "unconnected-(U1B-PA9-Pad30)") (class "Default")
      (node (ref "U1") (pin "30") (pinfunction "PA9_30") (pintype "bidirectional"))
    )
    (net (code "116") (name "unconnected-(U1B-PA10-Pad31)") (class "Default")
      (node (ref "U1") (pin "31") (pinfunction "PA10_31") (pintype "bidirectional"))
    )
    (net (code "117") (name "unconnected-(U1B-PA11-Pad32)") (class "Default")
      (node (ref "U1") (pin "32") (pinfunction "PA11_32") (pintype "bidirectional+no_connect"))
    )
    (net (code "118") (name "unconnected-(U1B-PA12-Pad33)") (class "Default")
      (node (ref "U1") (pin "33") (pinfunction "PA12_33") (pintype "bidirectional+no_connect"))
    )
    (net (code "119") (name "unconnected-(U1B-PB0-Pad18)") (class "Default")
      (node (ref "U1") (pin "18") (pinfunction "PB0_18") (pintype "bidirectional"))
    )
    (net (code "120") (name "unconnected-(U1B-PB2-Pad20)") (class "Default")
      (node (ref "U1") (pin "20") (pinfunction "PB2_20") (pintype "bidirectional+no_connect"))
    )
    (net (code "121") (name "unconnected-(U1B-PB3-Pad39)") (class "Default")
      (node (ref "U1") (pin "39") (pinfunction "PB3_39") (pintype "bidirectional+no_connect"))
    )
    (net (code "122") (name "unconnected-(U1B-PB5-Pad41)") (class "Default")
      (node (ref "U1") (pin "41") (pinfunction "PB5_41") (pintype "bidirectional"))
    )
    (net (code "123") (name "unconnected-(U1B-PB14-Pad27)") (class "Default")
      (node (ref "U1") (pin "27") (pinfunction "PB14_27") (pintype "bidirectional+no_connect"))
    )
    (net (code "124") (name "unconnected-(U1B-PC13-Pad2)") (class "Default")
      (node (ref "U1") (pin "2") (pinfunction "PC13_2") (pintype "bidirectional+no_connect"))
    )
    (net (code "125") (name "unconnected-(U2-A5-Pad6)") (class "Default")
      (node (ref "U2") (pin "6") (pinfunction "A5_6") (pintype "passive+no_connect"))
    )
    (net (code "126") (name "unconnected-(U2-A6-Pad7)") (class "Default")
      (node (ref "U2") (pin "7") (pinfunction "A6_7") (pintype "passive+no_connect"))
    )
    (net (code "127") (name "unconnected-(U2-B3-Pad17)") (class "Default")
      (node (ref "U2") (pin "17") (pinfunction "B3_17") (pintype "passive"))
    )
    (net (code "128") (name "unconnected-(U2-B4-Pad16)") (class "Default")
      (node (ref "U2") (pin "16") (pinfunction "B4_16") (pintype "passive"))
    )
    (net (code "129") (name "unconnected-(U2-B5-Pad15)") (class "Default")
      (node (ref "U2") (pin "15") (pinfunction "B5_15") (pintype "passive+no_connect"))
    )
    (net (code "130") (name "unconnected-(U2-B6-Pad14)") (class "Default")
      (node (ref "U2") (pin "14") (pinfunction "B6_14") (pintype "passive+no_connect"))
    )
    (net (code "131") (name "unconnected-(U3A-ADC0-Pad9)") (class "Default")
      (node (ref "U3") (pin "9") (pinfunction "ADC0_9") (pintype "passive+no_connect"))
    )
    (net (code "132") (name "unconnected-(U3A-NC-Pad2)") (class "Default")
      (node (ref "U3") (pin "2") (pinfunction "NC_2") (pintype "passive+no_connect"))
    )
    (net (code "133") (name "unconnected-(U3A-NC-Pad3)") (class "Default")
      (node (ref "U3") (pin "3") (pinfunction "NC_3") (pintype "passive+no_connect"))
    )
    (net (code "134") (name "unconnected-(U3A-NC-Pad4)") (class "Default")
      (node (ref "U3") (pin "4") (pinfunction "NC_4") (pintype "passive+no_connect"))
    )
    (net (code "135") (name "unconnected-(U3A-NC-Pad5)") (class "Default")
      (node (ref "U3") (pin "5") (pinfunction "NC_5") (pintype "passive+no_connect"))
    )
    (net (code "136") (name "unconnected-(U3A-NC-Pad6)") (class "Default")
      (node (ref "U3") (pin "6") (pinfunction "NC_6") (pintype "passive+no_connect"))
    )
    (net (code "137") (name "unconnected-(U3A-NC-Pad8)") (class "Default")
      (node (ref "U3") (pin "8") (pinfunction "NC_8") (pintype "passive+no_connect"))
    )
    (net (code "138") (name "unconnected-(U3A-NC-Pad21)") (class "Default")
      (node (ref "U3") (pin "21") (pinfunction "NC_21") (pintype "passive+no_connect"))
    )
    (net (code "139") (name "unconnected-(U3A-NC-Pad22)") (class "Default")
      (node (ref "U3") (pin "22") (pinfunction "NC_22") (pintype "passive+no_connect"))
    )
    (net (code "140") (name "unconnected-(U3A-NC-Pad23)") (class "Default")
      (node (ref "U3") (pin "23") (pinfunction "NC_23") (pintype "passive+no_connect"))
    )
    (net (code "141") (name "unconnected-(U3A-NC-Pad25)") (class "Default")
      (node (ref "U3") (pin "25") (pinfunction "NC_25") (pintype "passive+no_connect"))
    )
    (net (code "142") (name "unconnected-(U3A-NC-Pad26)") (class "Default")
      (node (ref "U3") (pin "26") (pinfunction "NC_26") (pintype "passive+no_connect"))
    )
    (net (code "143") (name "unconnected-(U3A-NC-Pad30)") (class "Default")
      (node (ref "U3") (pin "30") (pinfunction "NC_30") (pintype "passive+no_connect"))
    )
    (net (code "144") (name "unconnected-(U3A-NC-Pad31)") (class "Default")
      (node (ref "U3") (pin "31") (pinfunction "NC_31") (pintype "passive+no_connect"))
    )
    (net (code "145") (name "unconnected-(U3A-NC-Pad32)") (class "Default")
      (node (ref "U3") (pin "32") (pinfunction "NC_32") (pintype "passive+no_connect"))
    )
    (net (code "146") (name "unconnected-(U3A-NC-Pad33)") (class "Default")
      (node (ref "U3") (pin "33") (pinfunction "NC_33") (pintype "passive+no_connect"))
    )
    (net (code "147") (name "unconnected-(U3A-NC-Pad44)") (class "Default")
      (node (ref "U3") (pin "44") (pinfunction "NC_44") (pintype "passive+no_connect"))
    )
    (net (code "148") (name "unconnected-(U3A-PSM_EINT-Pad19)") (class "Default")
      (node (ref "U3") (pin "19") (pinfunction "PSM_EINT_19") (pintype "passive+no_connect"))
    )
    (net (code "149") (name "unconnected-(U3A-RXD_AUX-Pad28)") (class "Default")
      (node (ref "U3") (pin "28") (pinfunction "RXD_AUX_28") (pintype "passive+no_connect"))
    )
    (net (code "150") (name "unconnected-(U3A-TXD_AUX-Pad29)") (class "Default")
      (node (ref "U3") (pin "29") (pinfunction "TXD_AUX_29") (pintype "passive+no_connect"))
    )
    (net (code "151") (name "unconnected-(U3B-NC-Pad45)") (class "Default")
      (node (ref "U3") (pin "45") (pinfunction "NC_45") (pintype "passive+no_connect"))
    )
    (net (code "152") (name "unconnected-(U3B-NC-Pad46)") (class "Default")
      (node (ref "U3") (pin "46") (pinfunction "NC_46") (pintype "passive+no_connect"))
    )
    (net (code "153") (name "unconnected-(U3B-NC-Pad48)") (class "Default")
      (node (ref "U3") (pin "48") (pinfunction "NC_48") (pintype "passive+no_connect"))
    )
    (net (code "154") (name "unconnected-(U3B-NC-Pad52)") (class "Default")
      (node (ref "U3") (pin "52") (pinfunction "NC_52") (pintype "passive+no_connect"))
    )
    (net (code "155") (name "unconnected-(U3B-NC-Pad53)") (class "Default")
      (node (ref "U3") (pin "53") (pinfunction "NC_53") (pintype "passive+no_connect"))
    )
    (net (code "156") (name "unconnected-(U3B-NC-Pad54)") (class "Default")
      (node (ref "U3") (pin "54") (pinfunction "NC_54") (pintype "passive+no_connect"))
    )
    (net (code "157") (name "unconnected-(U3B-NC-Pad55)") (class "Default")
      (node (ref "U3") (pin "55") (pinfunction "NC_55") (pintype "passive+no_connect"))
    )
    (net (code "158") (name "unconnected-(U3B-NC-Pad56)") (class "Default")
      (node (ref "U3") (pin "56") (pinfunction "NC_56") (pintype "passive+no_connect"))
    )
    (net (code "159") (name "unconnected-(U3B-NC-Pad57)") (class "Default")
      (node (ref "U3") (pin "57") (pinfunction "NC_57") (pintype "passive+no_connect"))
    )
    (net (code "160") (name "unconnected-(U3B-NC-Pad58)") (class "Default")
      (node (ref "U3") (pin "58") (pinfunction "NC_58") (pintype "passive+no_connect"))
    )
    (net (code "161") (name "unconnected-(U3B-USB_DM-Pad51)") (class "Default")
      (node (ref "U3") (pin "51") (pinfunction "USB_DM_51") (pintype "passive+no_connect"))
    )
    (net (code "162") (name "unconnected-(U3B-USB_DP-Pad50)") (class "Default")
      (node (ref "U3") (pin "50") (pinfunction "USB_DP_50") (pintype "passive+no_connect"))
    )
    (net (code "163") (name "unconnected-(U3B-USB_MODE-Pad47)") (class "Default")
      (node (ref "U3") (pin "47") (pinfunction "USB_MODE_47") (pintype "passive+no_connect"))
    )
    (net (code "164") (name "unconnected-(U3B-VUSB_3V3-Pad49)") (class "Default")
      (node (ref "U3") (pin "49") (pinfunction "VUSB_3V3_49") (pintype "passive+no_connect"))
    )
    (net (code "165") (name "unconnected-(U7-IAN-Pad1)") (class "Default")
      (node (ref "U7") (pin "1") (pinfunction "IAN_1") (pintype "passive+no_connect"))
    )
    (net (code "166") (name "unconnected-(U7-IAP-Pad16)") (class "Default")
      (node (ref "U7") (pin "16") (pinfunction "IAP_16") (pintype "passive+no_connect"))
    )
    (net (code "167") (name "unconnected-(U8-NC-Pad1)") (class "Default")
      (node (ref "U8") (pin "1") (pinfunction "NC_1") (pintype "passive+no_connect"))
    )
    (net (code "168") (name "unconnected-(U8-NC-Pad2)") (class "Default")
      (node (ref "U8") (pin "2") (pinfunction "NC_2") (pintype "passive+no_connect"))
    )
  )
)
